# untitled.net
KiCad netlist of a schematic drawn in EAGLE
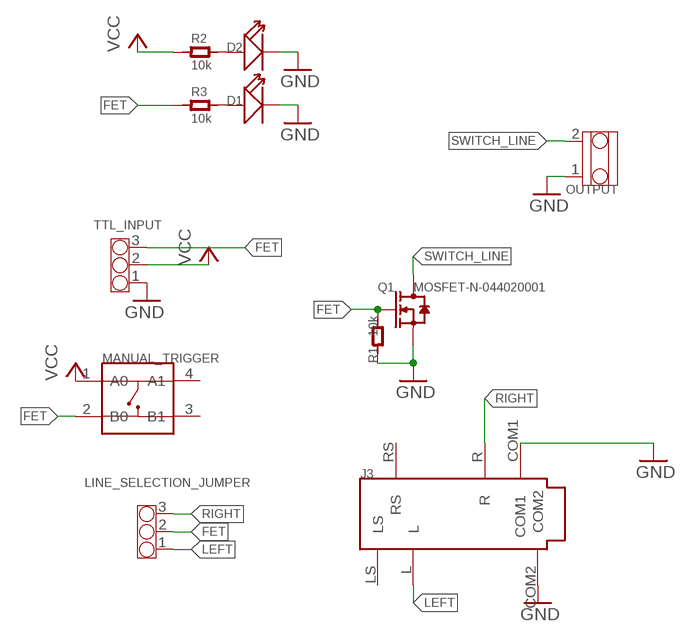
[diagram p0: schematic, sheet 1]

(export (version "E")
  (design (tool "Eeschema 10.0.6"))
  (components
    (comp (ref "D1")
      (value "LED")
      (footprint "eagle-import:LED0603")
      (libsource (lib "eagle-import") (part "LED"))
    )
    (comp (ref "D2")
      (value "LED")
      (footprint "eagle-import:LED0603")
      (libsource (lib "eagle-import") (part "LED"))
    )
    (comp (ref "J3")
      (value "AUDIO-CONNECTOR-6P-SMD-3440030P1")
      (footprint "eagle-import:6P-SMD-3.5")
      (libsource (lib "eagle-import") (part "AUDIO-CONNECTOR-6P-SMD-3440030P1"))
    )
    (comp (ref "LINE_SELECTION_JUMPER")
      (value "CONNECTOR-HEADER-3P-3460810P1")
      (footprint "eagle-import:1X3P-2.54-2.54-11.6-3.0-BLACK-MALE")
      (libsource (lib "eagle-import") (part "CONNECTOR-HEADER-3P-3460810P1"))
    )
    (comp (ref "MANUAL_TRIGGER")
      (value "manual data")
      (footprint "eagle-import:4P-SMD-6.0X6.0X5.0H")
      (libsource (lib "eagle-import") (part "BUTTON-4P-3100010P1"))
    )
    (comp (ref "OUTPUT")
      (value "SCREW-TERMINAL-2P-3470070P1")
      (footprint "eagle-import:2P-3.5")
      (libsource (lib "eagle-import") (part "SCREW-TERMINAL-2P-3470070P1"))
    )
    (comp (ref "Q1")
      (value "MOSFET-N-044020001")
      (footprint "eagle-import:SOT23")
      (libsource (lib "eagle-import") (part "MOSFET-N-044020001"))
    )
    (comp (ref "R1")
      (value "10k")
      (footprint "eagle-import:R0603")
      (libsource (lib "eagle-import") (part "R-0603"))
    )
    (comp (ref "R2")
      (value "10k")
      (footprint "eagle-import:R0603")
      (libsource (lib "eagle-import") (part "R-0603"))
    )
    (comp (ref "R3")
      (value "10k")
      (footprint "eagle-import:R0603")
      (libsource (lib "eagle-import") (part "R-0603"))
    )
    (comp (ref "TTL_INPUT")
      (value "CONNECTOR-HEADER-3P-3460810P1")
      (footprint "eagle-import:1X3P-2.54-2.54-11.6-3.0-BLACK-MALE")
      (libsource (lib "eagle-import") (part "CONNECTOR-HEADER-3P-3460810P1"))
    )
  )
  (nets
    (net (code "1") (name "FET") (class "Default")
      (node (ref "LINE_SELECTION_JUMPER") (pin "2") (pinfunction "2_2") (pintype "bidirectional"))
      (node (ref "MANUAL_TRIGGER") (pin "2") (pinfunction "B0_2") (pintype "bidirectional"))
      (node (ref "Q1") (pin "1") (pinfunction "G_1") (pintype "passive"))
      (node (ref "R1") (pin "2") (pinfunction "2_2") (pintype "bidirectional"))
      (node (ref "R3") (pin "1") (pinfunction "1_1") (pintype "bidirectional"))
      (node (ref "TTL_INPUT") (pin "3") (pinfunction "3_3") (pintype "bidirectional"))
    )
    (net (code "2") (name "GND") (class "Default")
      (node (ref "D1") (pin "-") (pinfunction "-_-") (pintype "passive"))
      (node (ref "D2") (pin "-") (pinfunction "-_-") (pintype "passive"))
      (node (ref "J3") (pin "COM1") (pinfunction "COM1_COM1") (pintype "bidirectional"))
      (node (ref "J3") (pin "COM2") (pinfunction "COM2_COM2") (pintype "bidirectional"))
      (node (ref "OUTPUT") (pin "1") (pinfunction "1_1") (pintype "bidirectional"))
      (node (ref "Q1") (pin "2") (pinfunction "S_2") (pintype "passive"))
      (node (ref "R1") (pin "1") (pinfunction "1_1") (pintype "bidirectional"))
      (node (ref "TTL_INPUT") (pin "1") (pinfunction "1_1") (pintype "bidirectional"))
    )
    (net (code "3") (name "LEFT") (class "Default")
      (node (ref "J3") (pin "L") (pinfunction "L_L") (pintype "bidirectional"))
      (node (ref "LINE_SELECTION_JUMPER") (pin "1") (pinfunction "1_1") (pintype "bidirectional"))
    )
    (net (code "4") (name "Net-(D1-Pad+)") (class "Default")
      (node (ref "D1") (pin "+") (pinfunction "+_+") (pintype "passive"))
      (node (ref "R3") (pin "2") (pinfunction "2_2") (pintype "bidirectional"))
    )
    (net (code "5") (name "Net-(D2-Pad+)") (class "Default")
      (node (ref "D2") (pin "+") (pinfunction "+_+") (pintype "passive"))
      (node (ref "R2") (pin "2") (pinfunction "2_2") (pintype "bidirectional"))
    )
    (net (code "6") (name "RIGHT") (class "Default")
      (node (ref "J3") (pin "R") (pinfunction "R_R") (pintype "bidirectional"))
      (node (ref "LINE_SELECTION_JUMPER") (pin "3") (pinfunction "3_3") (pintype "bidirectional"))
    )
    (net (code "7") (name "SWITCH_LINE") (class "Default")
      (node (ref "OUTPUT") (pin "2") (pinfunction "2_2") (pintype "bidirectional"))
      (node (ref "Q1") (pin "3") (pinfunction "D_3") (pintype "passive"))
    )
    (net (code "8") (name "VCC") (class "Default")
      (node (ref "MANUAL_TRIGGER") (pin "1") (pinfunction "A0_1") (pintype "bidirectional"))
      (node (ref "R2") (pin "1") (pinfunction "1_1") (pintype "bidirectional"))
      (node (ref "TTL_INPUT") (pin "2") (pinfunction "2_2") (pintype "bidirectional"))
    )
    (net (code "9") (name "unconnected-(J3-PadLS)") (class "Default")
      (node (ref "J3") (pin "LS") (pinfunction "LS_LS") (pintype "bidirectional"))
    )
    (net (code "10") (name "unconnected-(J3-PadRS)") (class "Default")
      (node (ref "J3") (pin "RS") (pinfunction "RS_RS") (pintype "bidirectional"))
    )
    (net (code "11") (name "unconnected-(MANUAL_TRIGGER-A1-Pad4)") (class "Default")
      (node (ref "MANUAL_TRIGGER") (pin "4") (pinfunction "A1_4") (pintype "bidirectional"))
    )
    (net (code "12") (name "unconnected-(MANUAL_TRIGGER-B1-Pad3)") (class "Default")
      (node (ref "MANUAL_TRIGGER") (pin "3") (pinfunction "B1_3") (pintype "bidirectional"))
    )
  )
)
